# 05_-_ADC.net
KiCad netlist of a schematic drawn in Altium Designer
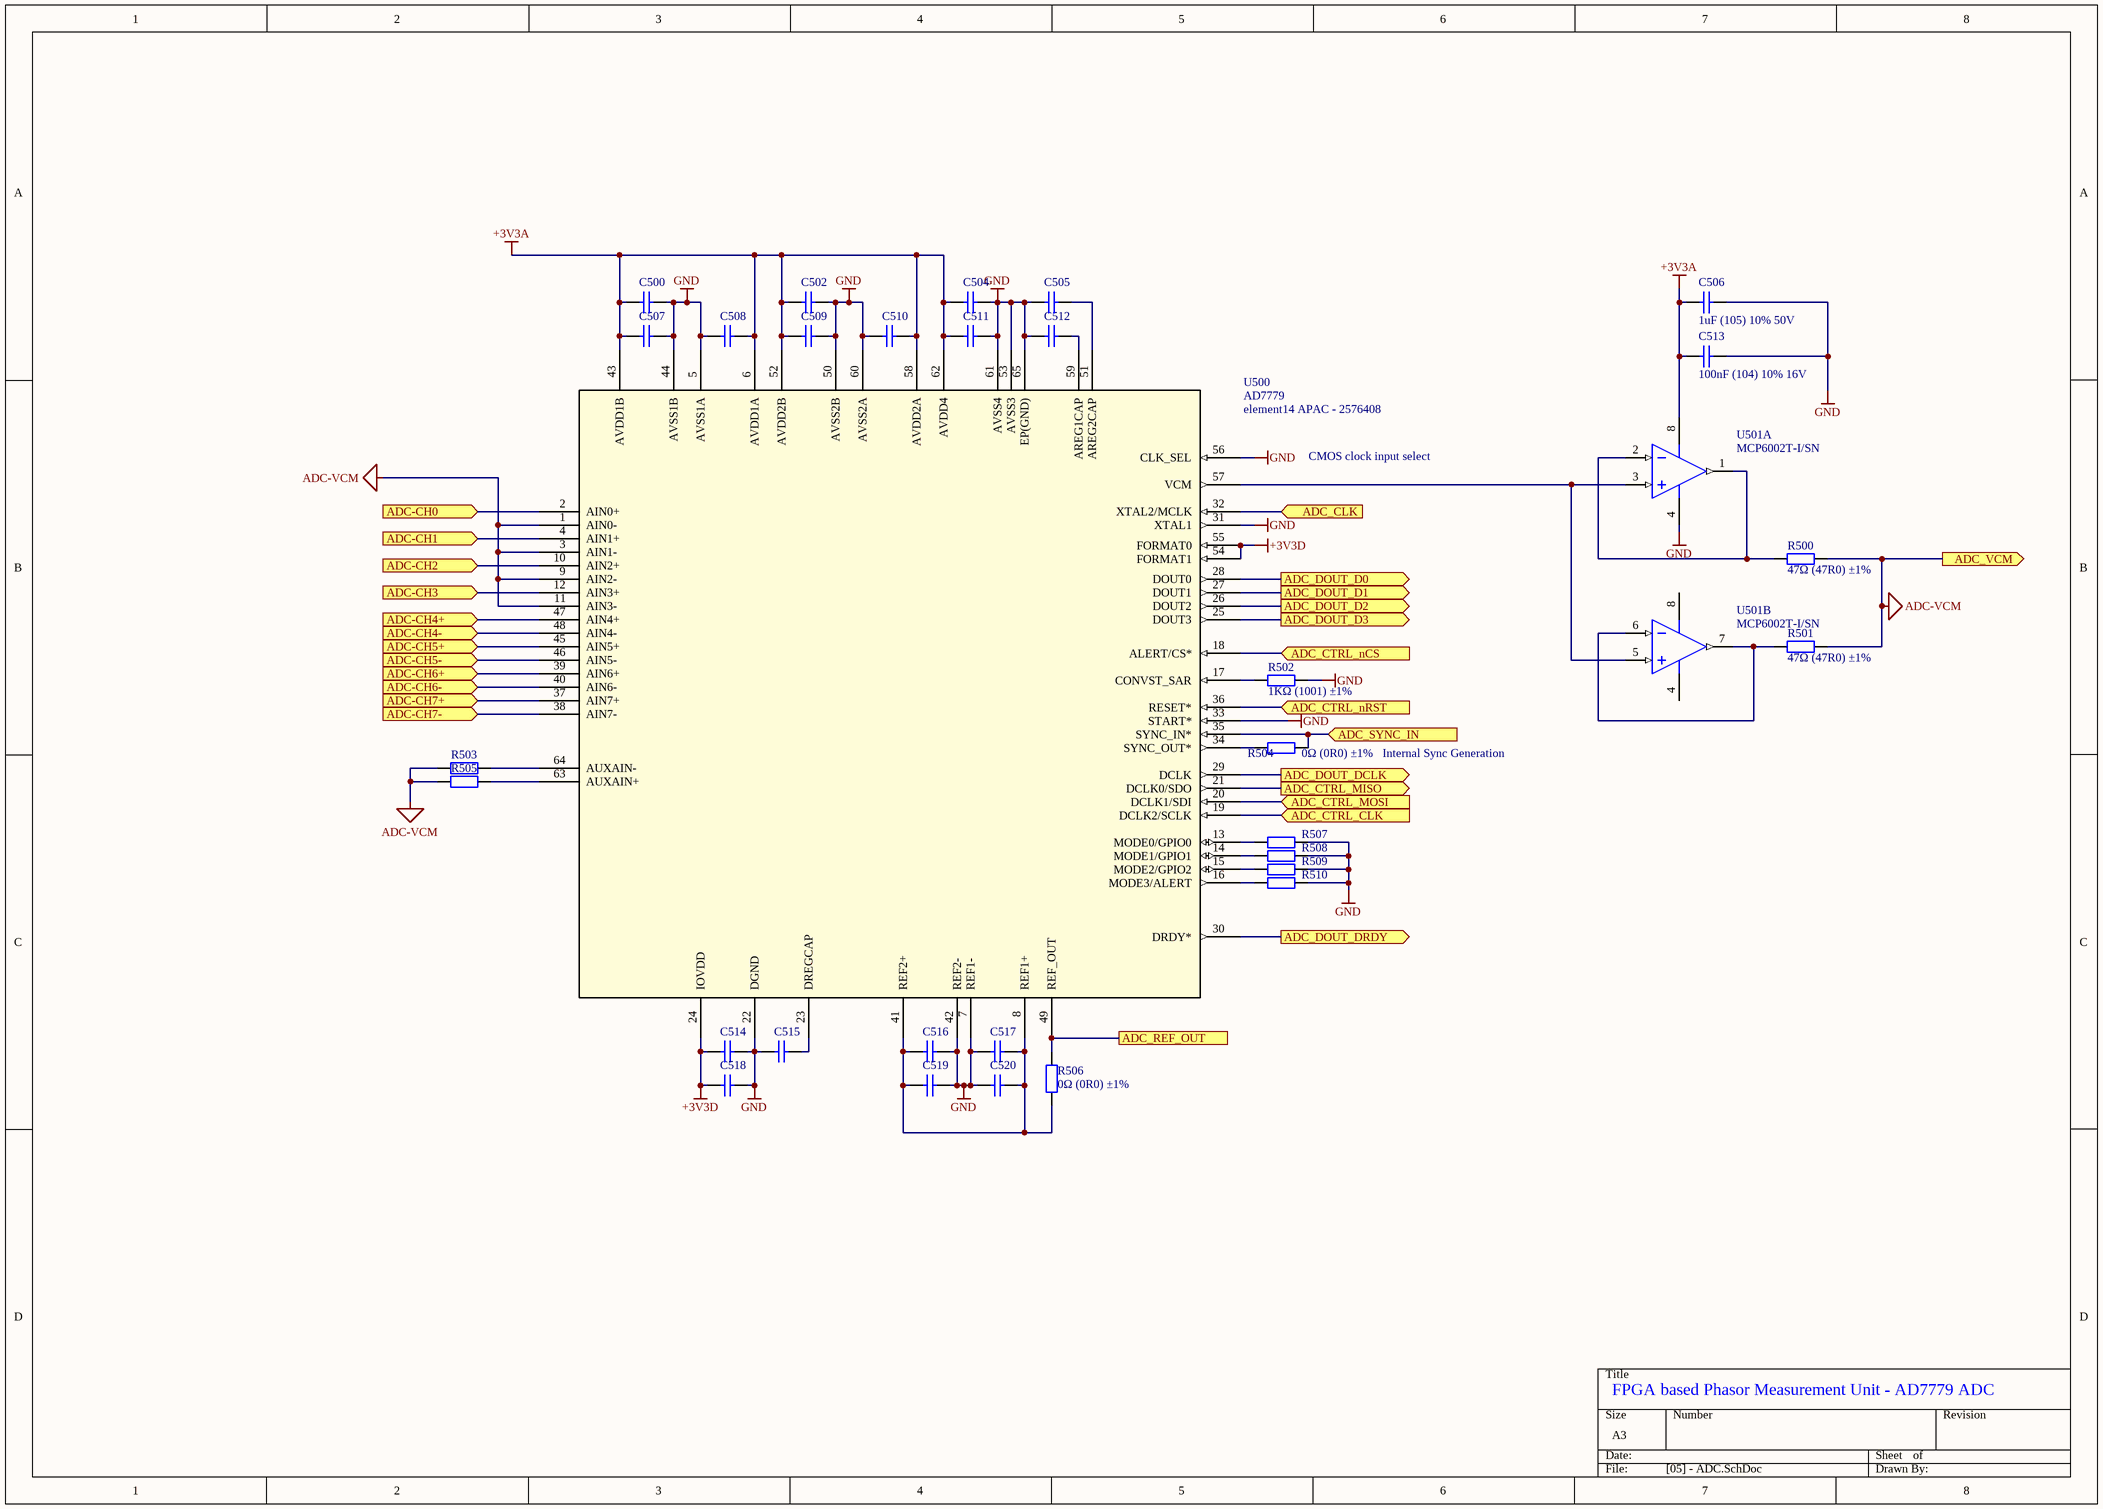
[diagram p0: [05] - ADC.SchDoc]

(export (version "E")
  (design (tool "Eeschema 10.0.6"))
  (components
    (comp (ref "C500")
      (value "1uF (105) 10% 50V")
      (footprint "0603_C")
      (description "贴片电容")
      (libsource (lib "Cap") (part "0603 1uF (105) 10% 50V"))
    )
    (comp (ref "C502")
      (value "1uF (105) 10% 50V")
      (footprint "0603_C")
      (description "贴片电容")
      (libsource (lib "Cap") (part "0603 1uF (105) 10% 50V"))
    )
    (comp (ref "C504")
      (value "1uF (105) 10% 50V")
      (footprint "0603_C")
      (description "贴片电容")
      (libsource (lib "Cap") (part "0603 1uF (105) 10% 50V"))
    )
    (comp (ref "C505")
      (value "100nF (104) 10% 16V")
      (footprint "0402_C")
      (description "贴片电容")
      (libsource (lib "Cap") (part "0402 100nF (104) 10% 16V"))
    )
    (comp (ref "C506")
      (value "1uF (105) 10% 50V")
      (footprint "0603_C")
      (description "贴片电容")
      (libsource (lib "Cap") (part "0603 1uF (105) 10% 50V"))
    )
    (comp (ref "C507")
      (value "100nF (104) 10% 16V")
      (footprint "0402_C")
      (description "贴片电容")
      (libsource (lib "Cap") (part "0402 100nF (104) 10% 16V"))
    )
    (comp (ref "C508")
      (value "100nF (104) 10% 16V")
      (footprint "0402_C")
      (description "贴片电容")
      (libsource (lib "Cap") (part "0402 100nF (104) 10% 16V"))
    )
    (comp (ref "C509")
      (value "100nF (104) 10% 16V")
      (footprint "0402_C")
      (description "贴片电容")
      (libsource (lib "Cap") (part "0402 100nF (104) 10% 16V"))
    )
    (comp (ref "C510")
      (value "100nF (104) 10% 16V")
      (footprint "0402_C")
      (description "贴片电容")
      (libsource (lib "Cap") (part "0402 100nF (104) 10% 16V"))
    )
    (comp (ref "C511")
      (value "100nF (104) 10% 16V")
      (footprint "0402_C")
      (description "贴片电容")
      (libsource (lib "Cap") (part "0402 100nF (104) 10% 16V"))
    )
    (comp (ref "C512")
      (value "100nF (104) 10% 16V")
      (footprint "0402_C")
      (description "贴片电容")
      (libsource (lib "Cap") (part "0402 100nF (104) 10% 16V"))
    )
    (comp (ref "C513")
      (value "100nF (104) 10% 16V")
      (footprint "0402_C")
      (description "贴片电容")
      (libsource (lib "Cap") (part "0402 100nF (104) 10% 16V"))
    )
    (comp (ref "C514")
      (value "100nF (104) 10% 16V")
      (footprint "0402_C")
      (description "贴片电容")
      (libsource (lib "Cap") (part "0402 100nF (104) 10% 16V"))
    )
    (comp (ref "C515")
      (value "100nF (104) 10% 16V")
      (footprint "0402_C")
      (description "贴片电容")
      (libsource (lib "Cap") (part "0402 100nF (104) 10% 16V"))
    )
    (comp (ref "C516")
      (value "100nF (104) 10% 16V")
      (footprint "0402_C")
      (description "贴片电容")
      (libsource (lib "Cap") (part "0402 100nF (104) 10% 16V"))
    )
    (comp (ref "C517")
      (value "100nF (104) 10% 16V")
      (footprint "0402_C")
      (description "贴片电容")
      (libsource (lib "Cap") (part "0402 100nF (104) 10% 16V"))
    )
    (comp (ref "C518")
      (value "1uF (105) 10% 50V")
      (footprint "0603_C")
      (description "贴片电容")
      (libsource (lib "Cap") (part "0603 1uF (105) 10% 50V"))
    )
    (comp (ref "C519")
      (value "1uF (105) 10% 50V")
      (footprint "0603_C")
      (description "贴片电容")
      (libsource (lib "Cap") (part "0603 1uF (105) 10% 50V"))
    )
    (comp (ref "C520")
      (value "1uF (105) 10% 50V")
      (footprint "0603_C")
      (description "贴片电容")
      (libsource (lib "Cap") (part "0603 1uF (105) 10% 50V"))
    )
    (comp (ref "R500")
      (value "47Ω (47R0) ±1%")
      (footprint "0603_R")
      (description "贴片电阻")
      (libsource (lib "RES") (part "0603 47Ω (47R0) 1%"))
    )
    (comp (ref "R501")
      (value "47Ω (47R0) ±1%")
      (footprint "0603_R")
      (description "贴片电阻")
      (libsource (lib "RES") (part "0603 47Ω (47R0) 1%"))
    )
    (comp (ref "R502")
      (value "1KΩ (1001) ±1%")
      (footprint "0402_R")
      (description "贴片电阻")
      (libsource (lib "RES") (part "0402 1KΩ (1001) 1%"))
    )
    (comp (ref "R503")
      (value "1KΩ (1001) ±1%")
      (footprint "0402_R")
      (description "贴片电阻")
      (libsource (lib "RES") (part "0402 1KΩ (1001) 1%"))
    )
    (comp (ref "R504")
      (value "0Ω (0R0) ±1%")
      (footprint "0402_R")
      (description "贴片电阻")
      (libsource (lib "RES") (part "0402 0Ω (0R0) 1%"))
    )
    (comp (ref "R505")
      (value "1KΩ (1001) ±1%")
      (footprint "0402_R")
      (description "贴片电阻")
      (libsource (lib "RES") (part "0402 1KΩ (1001) 1%"))
    )
    (comp (ref "R506")
      (value "0Ω (0R0) ±1%")
      (footprint "0402_R")
      (description "贴片电阻")
      (libsource (lib "") (part "0402 0Ω (0R0) 1%_1"))
    )
    (comp (ref "R507")
      (value "1KΩ (1001) ±1%")
      (footprint "0402_R")
      (description "贴片电阻")
      (libsource (lib "RES") (part "0402 1KΩ (1001) 1%"))
    )
    (comp (ref "R508")
      (value "1KΩ (1001) ±1%")
      (footprint "0402_R")
      (description "贴片电阻")
      (libsource (lib "RES") (part "0402 1KΩ (1001) 1%"))
    )
    (comp (ref "R509")
      (value "1KΩ (1001) ±1%")
      (footprint "0402_R")
      (description "贴片电阻")
      (libsource (lib "RES") (part "0402 1KΩ (1001) 1%"))
    )
    (comp (ref "R510")
      (value "1KΩ (1001) ±1%")
      (footprint "0402_R")
      (description "贴片电阻")
      (libsource (lib "RES") (part "0402 1KΩ (1001) 1%"))
    )
    (comp (ref "U500")
      (value "AD7779")
      (footprint "CP_64_15")
      (description "ADC - 8 Channel")
      (fields (field (name "SUPPLIER PART NUMBER 1") "element14 APAC - 2576408"))
      (libsource (lib "FPGA_PMU_lib") (part "AD7779ACPZ"))
    )
    (comp (ref "U501")
      (value "MCP6002T-I/SN")
      (footprint "SOIC-8_150mil")
      (description "运放")
      (libsource (lib "IC") (part "MCP6002T-I/SN_[C7377]"))
    )
  )
  (nets
    (net (code "1") (name "+3V3A") (class "Default")
      (node (ref "C500") (pin "1") (pinfunction "1_1") (pintype "passive"))
      (node (ref "C502") (pin "1") (pinfunction "1_1") (pintype "passive"))
      (node (ref "C504") (pin "1") (pinfunction "1_1") (pintype "passive"))
      (node (ref "C506") (pin "1") (pinfunction "1_1") (pintype "passive"))
      (node (ref "C507") (pin "1") (pinfunction "1_1") (pintype "passive"))
      (node (ref "C508") (pin "2") (pinfunction "2_2") (pintype "passive"))
      (node (ref "C509") (pin "1") (pinfunction "1_1") (pintype "passive"))
      (node (ref "C510") (pin "2") (pinfunction "2_2") (pintype "passive"))
      (node (ref "C511") (pin "1") (pinfunction "1_1") (pintype "passive"))
      (node (ref "C513") (pin "1") (pinfunction "1_1") (pintype "passive"))
      (node (ref "U500") (pin "43") (pinfunction "AVDD1B_43") (pintype "passive"))
      (node (ref "U500") (pin "52") (pinfunction "AVDD2B_52") (pintype "passive"))
      (node (ref "U500") (pin "58") (pinfunction "AVDD2A_58") (pintype "passive"))
      (node (ref "U500") (pin "6") (pinfunction "AVDD1A_6") (pintype "passive"))
      (node (ref "U500") (pin "62") (pinfunction "AVDD4_62") (pintype "passive"))
      (node (ref "U501") (pin "8") (pinfunction "VDD_8") (pintype "power_in"))
    )
    (net (code "2") (name "+3V3D") (class "Default")
      (node (ref "C514") (pin "1") (pinfunction "1_1") (pintype "passive"))
      (node (ref "C518") (pin "1") (pinfunction "1_1") (pintype "passive"))
      (node (ref "U500") (pin "24") (pinfunction "IOVDD_24") (pintype "passive"))
      (node (ref "U500") (pin "54") (pinfunction "FORMAT1_54") (pintype "input"))
      (node (ref "U500") (pin "55") (pinfunction "FORMAT0_55") (pintype "input"))
    )
    (net (code "3") (name "/ADC-CH0") (class "Default")
      (node (ref "U500") (pin "2") (pinfunction "AIN0+_2") (pintype "passive"))
    )
    (net (code "4") (name "/ADC-CH1") (class "Default")
      (node (ref "U500") (pin "4") (pinfunction "AIN1+_4") (pintype "passive"))
    )
    (net (code "5") (name "/ADC-CH2") (class "Default")
      (node (ref "U500") (pin "10") (pinfunction "AIN2+_10") (pintype "passive"))
    )
    (net (code "6") (name "/ADC-CH3") (class "Default")
      (node (ref "U500") (pin "12") (pinfunction "AIN3+_12") (pintype "passive"))
    )
    (net (code "7") (name "/ADC-CH4+") (class "Default")
      (node (ref "U500") (pin "47") (pinfunction "AIN4+_47") (pintype "passive"))
    )
    (net (code "8") (name "/ADC-CH4-") (class "Default")
      (node (ref "U500") (pin "48") (pinfunction "AIN4-_48") (pintype "passive"))
    )
    (net (code "9") (name "/ADC-CH5+") (class "Default")
      (node (ref "U500") (pin "45") (pinfunction "AIN5+_45") (pintype "passive"))
    )
    (net (code "10") (name "/ADC-CH5-") (class "Default")
      (node (ref "U500") (pin "46") (pinfunction "AIN5-_46") (pintype "passive"))
    )
    (net (code "11") (name "/ADC-CH6+") (class "Default")
      (node (ref "U500") (pin "39") (pinfunction "AIN6+_39") (pintype "passive"))
    )
    (net (code "12") (name "/ADC-CH6-") (class "Default")
      (node (ref "U500") (pin "40") (pinfunction "AIN6-_40") (pintype "passive"))
    )
    (net (code "13") (name "/ADC-CH7+") (class "Default")
      (node (ref "U500") (pin "37") (pinfunction "AIN7+_37") (pintype "passive"))
    )
    (net (code "14") (name "/ADC-CH7-") (class "Default")
      (node (ref "U500") (pin "38") (pinfunction "AIN7-_38") (pintype "passive"))
    )
    (net (code "15") (name "/ADC_CLK") (class "Default")
      (node (ref "U500") (pin "32") (pinfunction "XTAL2/MCLK_32") (pintype "input"))
    )
    (net (code "16") (name "/ADC_CTRL_CLK") (class "Default")
      (node (ref "U500") (pin "19") (pinfunction "DCLK2/SCLK_19") (pintype "input"))
    )
    (net (code "17") (name "/ADC_CTRL_MISO") (class "Default")
      (node (ref "U500") (pin "21") (pinfunction "DCLK0/SDO_21") (pintype "output"))
    )
    (net (code "18") (name "/ADC_CTRL_MOSI") (class "Default")
      (node (ref "U500") (pin "20") (pinfunction "DCLK1/SDI_20") (pintype "input"))
    )
    (net (code "19") (name "/ADC_CTRL_nCS") (class "Default")
      (node (ref "U500") (pin "18") (pinfunction "ALERT/CS*_18") (pintype "input"))
    )
    (net (code "20") (name "/ADC_CTRL_nRST") (class "Default")
      (node (ref "U500") (pin "36") (pinfunction "RESET*_36") (pintype "input"))
    )
    (net (code "21") (name "/ADC_DOUT_D0") (class "Default")
      (node (ref "U500") (pin "28") (pinfunction "DOUT0_28") (pintype "output"))
    )
    (net (code "22") (name "/ADC_DOUT_D1") (class "Default")
      (node (ref "U500") (pin "27") (pinfunction "DOUT1_27") (pintype "output"))
    )
    (net (code "23") (name "/ADC_DOUT_D2") (class "Default")
      (node (ref "U500") (pin "26") (pinfunction "DOUT2_26") (pintype "output"))
    )
    (net (code "24") (name "/ADC_DOUT_D3") (class "Default")
      (node (ref "U500") (pin "25") (pinfunction "DOUT3_25") (pintype "output"))
    )
    (net (code "25") (name "/ADC_DOUT_DCLK") (class "Default")
      (node (ref "U500") (pin "29") (pinfunction "DCLK_29") (pintype "output"))
    )
    (net (code "26") (name "/ADC_DOUT_DRDY") (class "Default")
      (node (ref "U500") (pin "30") (pinfunction "DRDY*_30") (pintype "output"))
    )
    (net (code "27") (name "/ADC_REF_OUT") (class "Default")
      (node (ref "R506") (pin "2") (pinfunction "2_2") (pintype "passive"))
      (node (ref "U500") (pin "49") (pinfunction "REF_OUT_49") (pintype "passive"))
    )
    (net (code "28") (name "/ADC_SYNC_IN") (class "Default")
      (node (ref "R504") (pin "2") (pinfunction "2_2") (pintype "passive"))
      (node (ref "U500") (pin "35") (pinfunction "SYNC_IN*_35") (pintype "input"))
    )
    (net (code "29") (name "ADC-VCM") (class "Default")
      (node (ref "R500") (pin "2") (pinfunction "2_2") (pintype "passive"))
      (node (ref "R501") (pin "2") (pinfunction "2_2") (pintype "passive"))
      (node (ref "R503") (pin "1") (pinfunction "1_1") (pintype "passive"))
      (node (ref "R505") (pin "1") (pinfunction "1_1") (pintype "passive"))
      (node (ref "U500") (pin "1") (pinfunction "AIN0-_1") (pintype "passive"))
      (node (ref "U500") (pin "11") (pinfunction "AIN3-_11") (pintype "passive"))
      (node (ref "U500") (pin "3") (pinfunction "AIN1-_3") (pintype "passive"))
      (node (ref "U500") (pin "9") (pinfunction "AIN2-_9") (pintype "passive"))
    )
    (net (code "30") (name "GND") (class "Default")
      (node (ref "C500") (pin "2") (pinfunction "2_2") (pintype "passive"))
      (node (ref "C502") (pin "2") (pinfunction "2_2") (pintype "passive"))
      (node (ref "C504") (pin "2") (pinfunction "2_2") (pintype "passive"))
      (node (ref "C505") (pin "1") (pinfunction "1_1") (pintype "passive"))
      (node (ref "C506") (pin "2") (pinfunction "2_2") (pintype "passive"))
      (node (ref "C507") (pin "2") (pinfunction "2_2") (pintype "passive"))
      (node (ref "C508") (pin "1") (pinfunction "1_1") (pintype "passive"))
      (node (ref "C509") (pin "2") (pinfunction "2_2") (pintype "passive"))
      (node (ref "C510") (pin "1") (pinfunction "1_1") (pintype "passive"))
      (node (ref "C511") (pin "2") (pinfunction "2_2") (pintype "passive"))
      (node (ref "C512") (pin "1") (pinfunction "1_1") (pintype "passive"))
      (node (ref "C513") (pin "2") (pinfunction "2_2") (pintype "passive"))
      (node (ref "C514") (pin "2") (pinfunction "2_2") (pintype "passive"))
      (node (ref "C515") (pin "1") (pinfunction "1_1") (pintype "passive"))
      (node (ref "C516") (pin "2") (pinfunction "2_2") (pintype "passive"))
      (node (ref "C517") (pin "1") (pinfunction "1_1") (pintype "passive"))
      (node (ref "C518") (pin "2") (pinfunction "2_2") (pintype "passive"))
      (node (ref "C519") (pin "2") (pinfunction "2_2") (pintype "passive"))
      (node (ref "C520") (pin "1") (pinfunction "1_1") (pintype "passive"))
      (node (ref "R502") (pin "2") (pinfunction "2_2") (pintype "passive"))
      (node (ref "R507") (pin "2") (pinfunction "2_2") (pintype "passive"))
      (node (ref "R508") (pin "2") (pinfunction "2_2") (pintype "passive"))
      (node (ref "R509") (pin "2") (pinfunction "2_2") (pintype "passive"))
      (node (ref "R510") (pin "2") (pinfunction "2_2") (pintype "passive"))
      (node (ref "U500") (pin "22") (pinfunction "DGND_22") (pintype "passive"))
      (node (ref "U500") (pin "31") (pinfunction "XTAL1_31") (pintype "output"))
      (node (ref "U500") (pin "33") (pinfunction "START*_33") (pintype "input"))
      (node (ref "U500") (pin "42") (pinfunction "REF2-_42") (pintype "passive"))
      (node (ref "U500") (pin "44") (pinfunction "AVSS1B_44") (pintype "passive"))
      (node (ref "U500") (pin "5") (pinfunction "AVSS1A_5") (pintype "passive"))
      (node (ref "U500") (pin "50") (pinfunction "AVSS2B_50") (pintype "passive"))
      (node (ref "U500") (pin "53") (pinfunction "AVSS3_53") (pintype "passive"))
      (node (ref "U500") (pin "56") (pinfunction "CLK_SEL_56") (pintype "input"))
      (node (ref "U500") (pin "60") (pinfunction "AVSS2A_60") (pintype "passive"))
      (node (ref "U500") (pin "61") (pinfunction "AVSS4_61") (pintype "passive"))
      (node (ref "U500") (pin "65") (pinfunction "EP(GND)_65") (pintype "passive"))
      (node (ref "U500") (pin "7") (pinfunction "REF1-_7") (pintype "passive"))
      (node (ref "U501") (pin "4") (pinfunction "VSS_4") (pintype "power_in"))
    )
    (net (code "31") (name "Net-(U500-AREG1CAP)") (class "Default")
      (node (ref "C512") (pin "2") (pinfunction "2_2") (pintype "passive"))
      (node (ref "U500") (pin "59") (pinfunction "AREG1CAP_59") (pintype "passive"))
    )
    (net (code "32") (name "Net-(U500-AREG2CAP)") (class "Default")
      (node (ref "C505") (pin "2") (pinfunction "2_2") (pintype "passive"))
      (node (ref "U500") (pin "51") (pinfunction "AREG2CAP_51") (pintype "passive"))
    )
    (net (code "33") (name "Net-(U500-AUXAIN+)") (class "Default")
      (node (ref "R505") (pin "2") (pinfunction "2_2") (pintype "passive"))
      (node (ref "U500") (pin "63") (pinfunction "AUXAIN+_63") (pintype "passive"))
    )
    (net (code "34") (name "Net-(U500-AUXAIN-)") (class "Default")
      (node (ref "R503") (pin "2") (pinfunction "2_2") (pintype "passive"))
      (node (ref "U500") (pin "64") (pinfunction "AUXAIN-_64") (pintype "passive"))
    )
    (net (code "35") (name "Net-(U500-CONVST_SAR)") (class "Default")
      (node (ref "R502") (pin "1") (pinfunction "1_1") (pintype "passive"))
      (node (ref "U500") (pin "17") (pinfunction "CONVST_SAR_17") (pintype "input"))
    )
    (net (code "36") (name "Net-(U500-DREGCAP)") (class "Default")
      (node (ref "C515") (pin "2") (pinfunction "2_2") (pintype "passive"))
      (node (ref "U500") (pin "23") (pinfunction "DREGCAP_23") (pintype "passive"))
    )
    (net (code "37") (name "Net-(U500-MODE0{slash}GPIO0)") (class "Default")
      (node (ref "R507") (pin "1") (pinfunction "1_1") (pintype "passive"))
      (node (ref "U500") (pin "13") (pinfunction "MODE0/GPIO0_13") (pintype "bidirectional"))
    )
    (net (code "38") (name "Net-(U500-MODE1{slash}GPIO1)") (class "Default")
      (node (ref "R508") (pin "1") (pinfunction "1_1") (pintype "passive"))
      (node (ref "U500") (pin "14") (pinfunction "MODE1/GPIO1_14") (pintype "bidirectional"))
    )
    (net (code "39") (name "Net-(U500-MODE2{slash}GPIO2)") (class "Default")
      (node (ref "R509") (pin "1") (pinfunction "1_1") (pintype "passive"))
      (node (ref "U500") (pin "15") (pinfunction "MODE2/GPIO2_15") (pintype "bidirectional"))
    )
    (net (code "40") (name "Net-(U500-MODE3{slash}ALERT)") (class "Default")
      (node (ref "R510") (pin "1") (pinfunction "1_1") (pintype "passive"))
      (node (ref "U500") (pin "16") (pinfunction "MODE3/ALERT_16") (pintype "output"))
    )
    (net (code "41") (name "Net-(U500-REF1+)") (class "Default")
      (node (ref "C516") (pin "1") (pinfunction "1_1") (pintype "passive"))
      (node (ref "C517") (pin "2") (pinfunction "2_2") (pintype "passive"))
      (node (ref "C519") (pin "1") (pinfunction "1_1") (pintype "passive"))
      (node (ref "C520") (pin "2") (pinfunction "2_2") (pintype "passive"))
      (node (ref "R506") (pin "1") (pinfunction "1_1") (pintype "passive"))
      (node (ref "U500") (pin "41") (pinfunction "REF2+_41") (pintype "passive"))
      (node (ref "U500") (pin "8") (pinfunction "REF1+_8") (pintype "passive"))
    )
    (net (code "42") (name "Net-(U500-SYNC_OUT*)") (class "Default")
      (node (ref "R504") (pin "1") (pinfunction "1_1") (pintype "passive"))
      (node (ref "U500") (pin "34") (pinfunction "SYNC_OUT*_34") (pintype "output"))
    )
    (net (code "43") (name "Net-(U500-VCM)") (class "Default")
      (node (ref "U500") (pin "57") (pinfunction "VCM_57") (pintype "output"))
      (node (ref "U501") (pin "3") (pinfunction "VINA+_3") (pintype "input"))
      (node (ref "U501") (pin "5") (pinfunction "VINB+_5") (pintype "input"))
    )
    (net (code "44") (name "Net-(U501A-VINA-)") (class "Default")
      (node (ref "R500") (pin "1") (pinfunction "1_1") (pintype "passive"))
      (node (ref "U501") (pin "1") (pinfunction "VOUTA_1") (pintype "output"))
      (node (ref "U501") (pin "2") (pinfunction "VINA-_2") (pintype "input"))
    )
    (net (code "45") (name "Net-(U501B-VINB-)") (class "Default")
      (node (ref "R501") (pin "1") (pinfunction "1_1") (pintype "passive"))
      (node (ref "U501") (pin "6") (pinfunction "VINB-_6") (pintype "input"))
      (node (ref "U501") (pin "7") (pinfunction "VOUTB_7") (pintype "output"))
    )
    (net (code "46") (name "unconnected-(U501B-VDD-Pad8)") (class "Default")
      (node (ref "U501") (pin "8") (pinfunction "VDD_8") (pintype "power_in"))
    )
    (net (code "47") (name "unconnected-(U501B-VSS-Pad4)") (class "Default")
      (node (ref "U501") (pin "4") (pinfunction "VSS_4") (pintype "power_in"))
    )
  )
)
